# Sheet2.net
KiCad netlist of a schematic drawn in Altium Designer
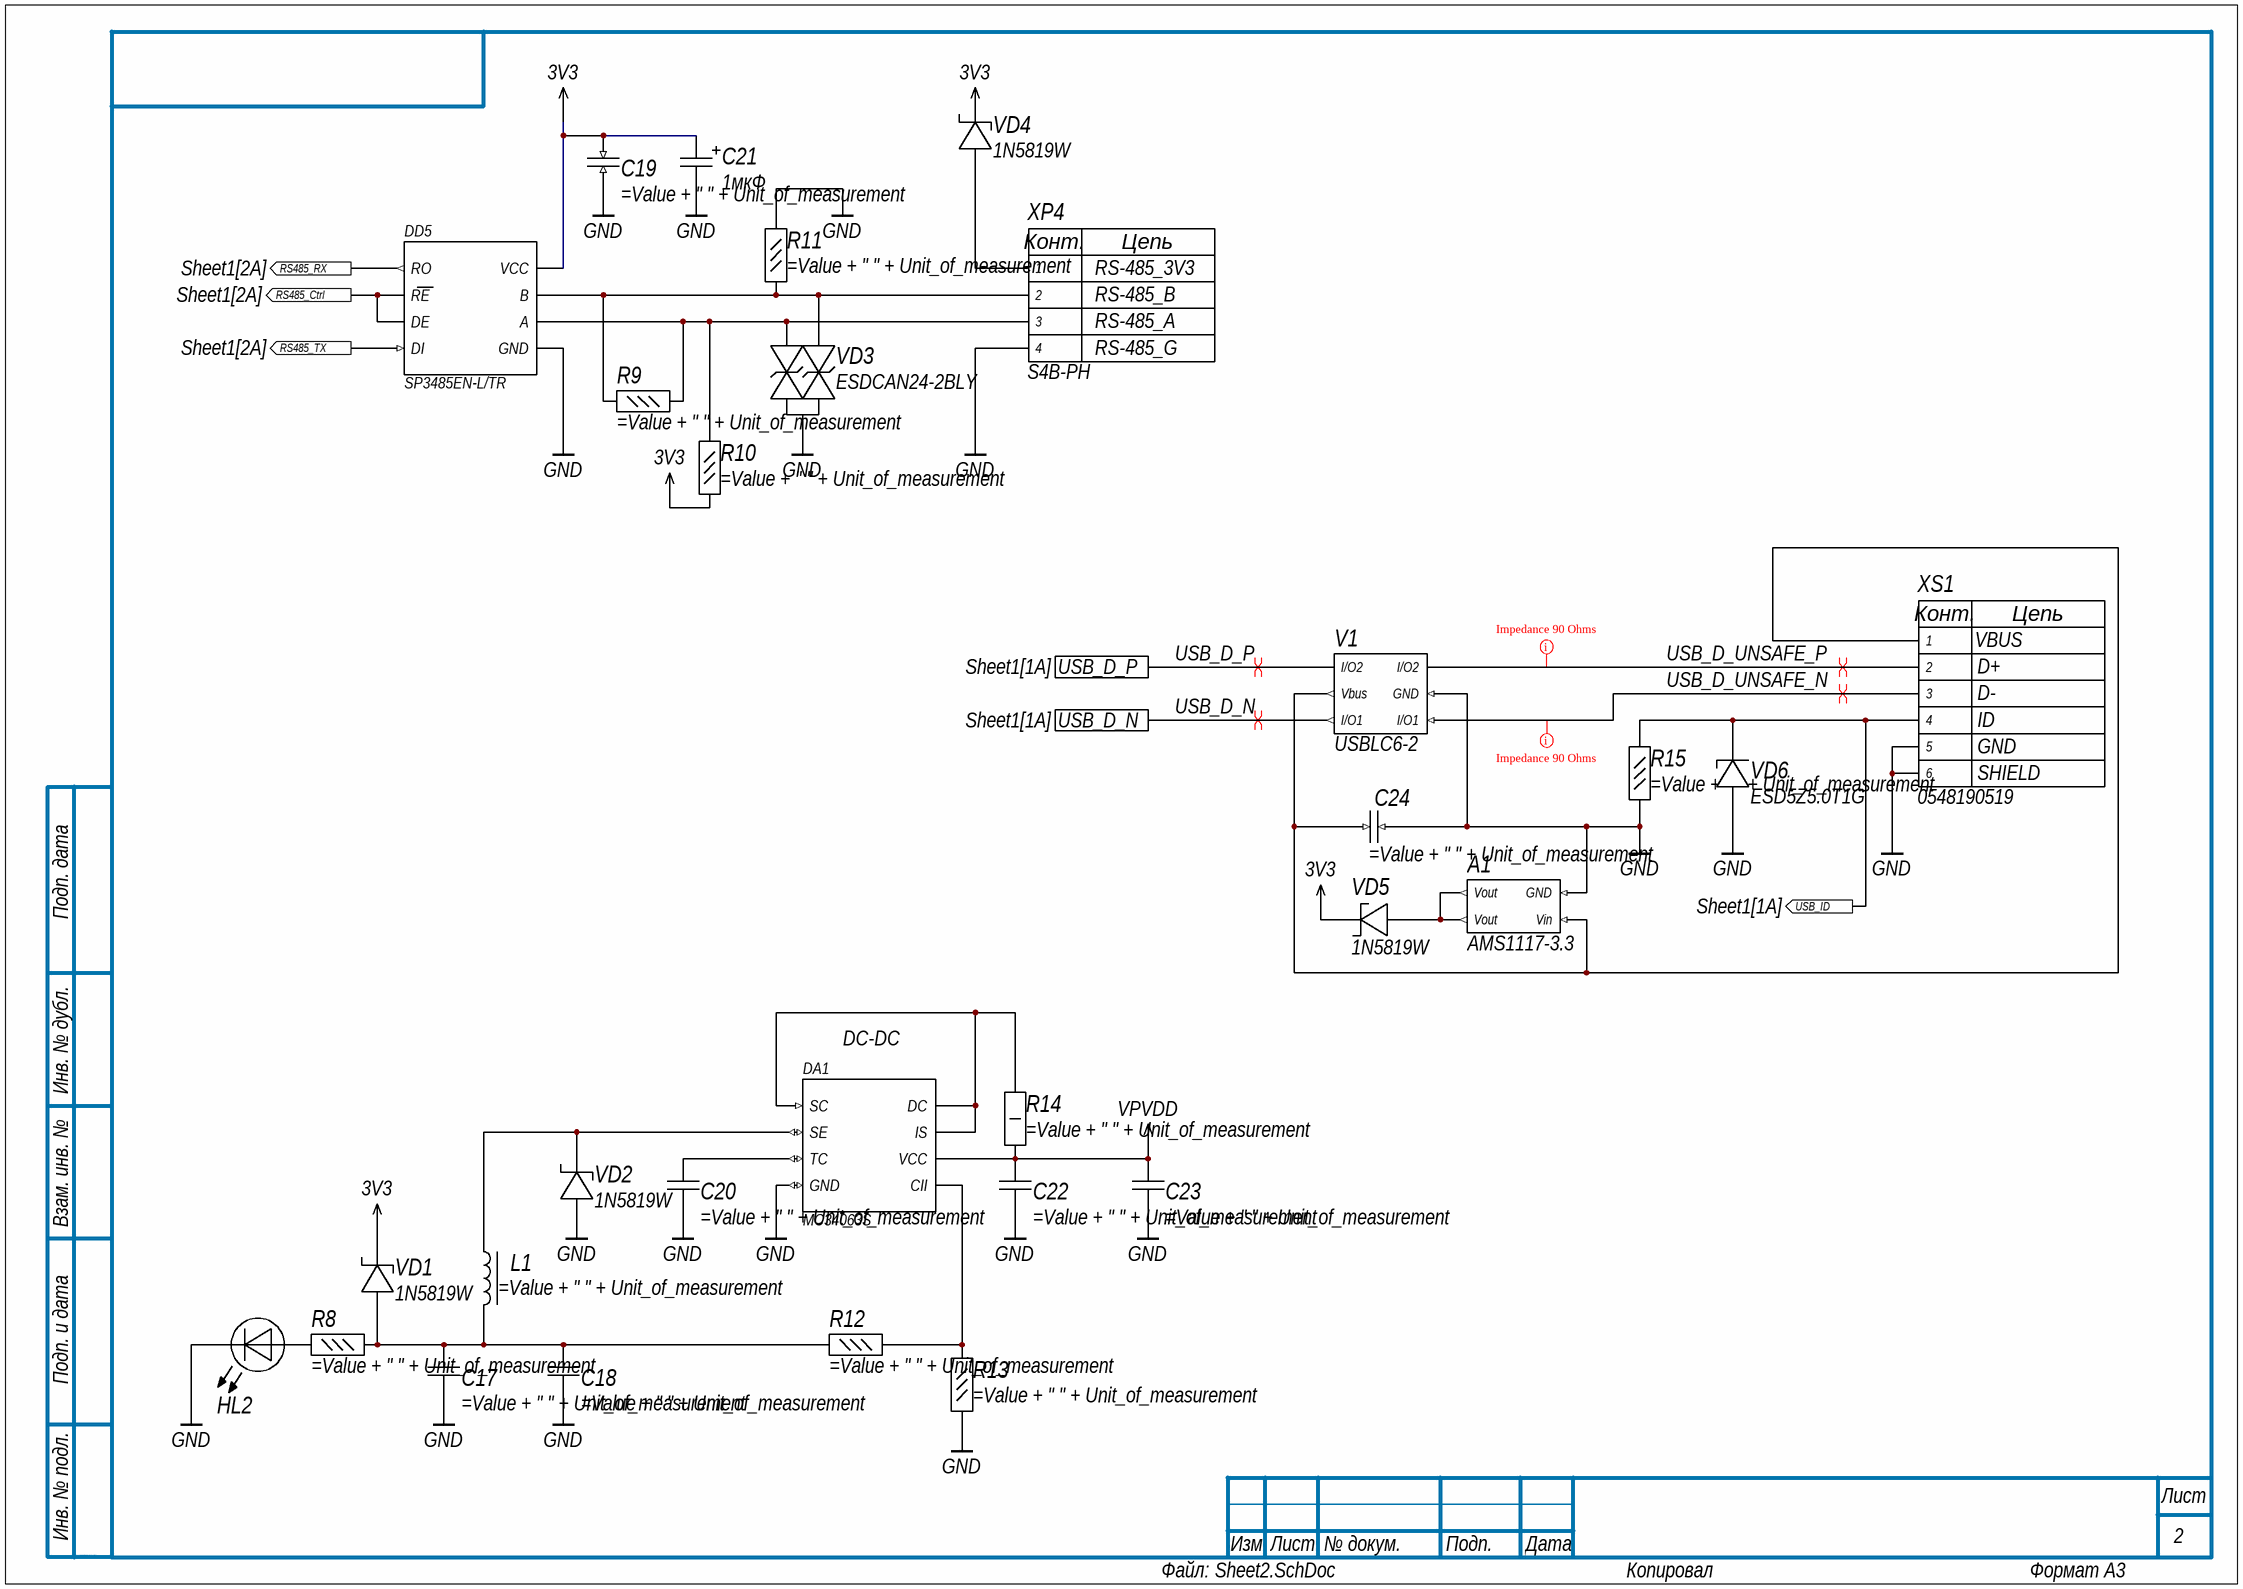
[diagram p0: Sheet2.SchDoc]

(export (version "E")
  (design (tool "Eeschema 10.0.6"))
  (components
    (comp (ref "A1")
      (value "AMS1117-3.3")
      (footprint "SOT-223")
      (description "Линейный регулятор с малым падением напряжения, 1А, 3.3В [SOT-223]")
      (libsource (lib "ICs") (part "AMS1117-3.3"))
    )
    (comp (ref "C17")
      (value "10мкФ 50В")
      (footprint "CAP_1206")
      (description "Конденсатор керамический, типоразмера 1206")
      (libsource (lib "SimpleComponents") (part "CAP_1206"))
    )
    (comp (ref "C18")
      (value "10мкФ 50В")
      (footprint "CAP_1206")
      (description "Конденсатор керамический, типоразмера 1206")
      (libsource (lib "SimpleComponents") (part "CAP_1206"))
    )
    (comp (ref "C19")
      (value "100нФ")
      (footprint "CAP_0603")
      (description "Конденсатор керамический, типоразмера 0603")
      (libsource (lib "PassiveComponents") (part "CAP_0603"))
    )
    (comp (ref "C20")
      (value "3.9нФ")
      (footprint "CAP_0603")
      (description "Конденсатор керамический, типоразмера 0603")
      (libsource (lib "SimpleComponents") (part "CAP_0603"))
    )
    (comp (ref "C21")
      (value "1мкФ")
      (footprint "TECAP_A")
      (description "Описание свойств компонента")
      (libsource (lib "PassiveComponents") (part "TECAP_A"))
    )
    (comp (ref "C22")
      (value "10мкФ 50В")
      (footprint "CAP_1206")
      (description "Конденсатор керамический, типоразмера 1206")
      (libsource (lib "SimpleComponents") (part "CAP_1206"))
    )
    (comp (ref "C23")
      (value "10мкФ 50В")
      (footprint "CAP_1206")
      (description "Конденсатор керамический, типоразмера 1206")
      (libsource (lib "SimpleComponents") (part "CAP_1206"))
    )
    (comp (ref "C24")
      (value "100нФ")
      (footprint "CAP_0603")
      (description "Конденсатор керамический, типоразмера 0603")
      (libsource (lib "PassiveComponents") (part "CAP_0603"))
    )
    (comp (ref "DA1")
      (value "MC34063S")
      (footprint "SOP-8 WithoutTP")
      (libsource (lib "ICs") (part "MC34063S"))
    )
    (comp (ref "DD5")
      (value "SP3485EN-L/TR")
      (footprint "SOIC-8 WIthoutTP")
      (description "Трансивер RS485 Half-Duplex 1/1")
      (libsource (lib "ICs") (part "SP3485EN"))
    )
    (comp (ref "HL2") (value "3") (footprint "LED_0805") (libsource (lib "Complicated") (part "LED_0805_R")))
    (comp (ref "L1")
      (value "47мкГн")
      (footprint "CD54")
      (description "Резистор, типоразмера 2010")
      (libsource (lib "SimpleComponents") (part "IND_CD54"))
    )
    (comp (ref "R8")
      (value "330Ом")
      (footprint "RES_0603")
      (description "Резистор, типоразмера 0603")
      (libsource (lib "") (part "RES_0603_2"))
    )
    (comp (ref "R9")
      (value "120Ом")
      (footprint "RES_0603")
      (description "Резистор, типоразмера 0603")
      (libsource (lib "SimpleComponents") (part "RES_0603"))
    )
    (comp (ref "R10")
      (value "4.7кОм")
      (footprint "RES_0603")
      (description "Резистор, типоразмера 0603")
      (libsource (lib "") (part "RES_0603_3"))
    )
    (comp (ref "R11")
      (value "4.7кОм")
      (footprint "RES_0603")
      (description "Резистор, типоразмера 0603")
      (libsource (lib "") (part "RES_0603_1"))
    )
    (comp (ref "R12")
      (value "8.2кОм 1%")
      (footprint "RES_0603")
      (description "Резистор, типоразмера 0603")
      (libsource (lib "SimpleComponents") (part "RES_0603"))
    )
    (comp (ref "R13")
      (value "5кОм 1%")
      (footprint "RES_0603")
      (description "Резистор, типоразмера 0603")
      (libsource (lib "") (part "RES_0603_1"))
    )
    (comp (ref "R14")
      (value "0.2Ом 1%")
      (footprint "RES_2512")
      (description "Резистор, типоразмера 2512")
      (libsource (lib "SimpleComponents") (part "RES_2512"))
    )
    (comp (ref "R15")
      (value "100кОм")
      (footprint "RES_0603")
      (description "Резистор, типоразмера 0603")
      (libsource (lib "") (part "RES_0603_1"))
    )
    (comp (ref "V1")
      (value "USBLC6-2")
      (footprint "SOT23-6")
      (description "Защита интерфейса USB от электростатических разрядов [SOT-23-6]")
      (libsource (lib "ICs") (part "USBLC6-2"))
    )
    (comp (ref "VD1")
      (value "1N5819W")
      (footprint "SOD-123")
      (description "Диод Шоттки, 40 В, 0.35 А, SOD-123")
      (libsource (lib "SimpleComponents") (part "1N5819W"))
    )
    (comp (ref "VD2")
      (value "1N5819W")
      (footprint "SOD-123")
      (description "Диод Шоттки, 40 В, 0.35 А, SOD-123")
      (libsource (lib "SimpleComponents") (part "1N5819W"))
    )
    (comp (ref "VD3")
      (value "ESDCAN24-2BLY")
      (footprint "SOT23")
      (description "Устройство защиты CAN шины от ESD, 2 защитных диода [SOT-23-3]")
      (libsource (lib "Complicated") (part "ESDCAN24-2BLY"))
    )
    (comp (ref "VD4")
      (value "1N5819W")
      (footprint "SOD-123")
      (description "Диод Шоттки, 40 В, 0.35 А, SOD-123")
      (libsource (lib "SimpleComponents") (part "1N5819W"))
    )
    (comp (ref "VD5")
      (value "1N5819W")
      (footprint "SOD-123")
      (description "Диод Шоттки, 40 В, 0.35 А, SOD-123")
      (libsource (lib "Complicated") (part "1N5819W"))
    )
    (comp (ref "VD6")
      (value "ESD5Z5.0T1G")
      (footprint "SOD-523")
      (description "Устройство защиты от ESD, защитный диод, 5В [SOD-523]")
      (libsource (lib "Complicated") (part "ESD5Z5.0T1G"))
    )
    (comp (ref "XP4")
      (value "S4B-PH")
      (footprint "S4B-PH")
      (description "JST PH 4pin 2 mm pitch; horizontal; through hole OR full smd; S4B-PH-SM4-TB")
      (libsource (lib "SimpleComponents") (part "S4B-PH"))
    )
    (comp (ref "XS1")
      (value "0548190519")
      (footprint "USB_Mini_B_TH")
      (description "USB - mini B USB 2.0 OTG Receptacle Connector 5 Position Through Hole, Right Angle")
      (libsource (lib "SimpleComponents") (part "0548190519"))
    )
  )
  (nets
    (net (code "1") (name "/RS485_Ctrl") (class "Default")
      (node (ref "DD5") (pin "2") (pinfunction "RE_2") (pintype "passive"))
      (node (ref "DD5") (pin "3") (pinfunction "DE_3") (pintype "passive"))
    )
    (net (code "2") (name "/RS485_RX") (class "Default")
      (node (ref "DD5") (pin "1") (pinfunction "RO_1") (pintype "output"))
    )
    (net (code "3") (name "/RS485_TX") (class "Default")
      (node (ref "DD5") (pin "4") (pinfunction "DI_4") (pintype "input"))
    )
    (net (code "4") (name "/USB_D_N") (class "Default")
      (node (ref "V1") (pin "6") (pinfunction "I/O1_6") (pintype "output"))
    )
    (net (code "5") (name "/USB_D_P") (class "Default")
      (node (ref "V1") (pin "4") (pinfunction "I/O2_4") (pintype "power_in"))
    )
    (net (code "6") (name "/USB_D_UNSAFE_N") (class "Default")
      (node (ref "V1") (pin "1") (pinfunction "I/O1_1") (pintype "input"))
      (node (ref "XS1") (pin "4") (pinfunction "3_4") (pintype "passive"))
    )
    (net (code "7") (name "/USB_D_UNSAFE_P") (class "Default")
      (node (ref "V1") (pin "3") (pinfunction "I/O2_3") (pintype "power_in"))
      (node (ref "XS1") (pin "3") (pinfunction "2_3") (pintype "passive"))
    )
    (net (code "8") (name "/USB_ID") (class "Default")
      (node (ref "R15") (pin "2") (pinfunction "2_2") (pintype "passive"))
      (node (ref "VD6") (pin "1") (pinfunction "1_1") (pintype "passive"))
      (node (ref "XS1") (pin "2") (pinfunction "4_2") (pintype "passive"))
    )
    (net (code "9") (name "3V3") (class "Default")
      (node (ref "C19") (pin "2") (pintype "input"))
      (node (ref "C21") (pin "1") (pintype "passive"))
      (node (ref "DD5") (pin "8") (pinfunction "VCC_8") (pintype "power_in"))
      (node (ref "R10") (pin "2") (pinfunction "2_2") (pintype "passive"))
      (node (ref "VD1") (pin "1") (pinfunction "1_1") (pintype "passive"))
      (node (ref "VD4") (pin "1") (pinfunction "1_1") (pintype "passive"))
      (node (ref "VD5") (pin "1") (pinfunction "1_1") (pintype "passive"))
    )
    (net (code "10") (name "GND") (class "Default")
      (node (ref "A1") (pin "1") (pinfunction "GND_1") (pintype "input"))
      (node (ref "C17") (pin "1") (pintype "passive"))
      (node (ref "C18") (pin "1") (pintype "passive"))
      (node (ref "C19") (pin "1") (pintype "input"))
      (node (ref "C20") (pin "1") (pintype "passive"))
      (node (ref "C21") (pin "2") (pintype "passive"))
      (node (ref "C22") (pin "1") (pintype "passive"))
      (node (ref "C23") (pin "1") (pintype "passive"))
      (node (ref "C24") (pin "1") (pintype "input"))
      (node (ref "DA1") (pin "4") (pinfunction "GND_4") (pintype "bidirectional"))
      (node (ref "DD5") (pin "5") (pinfunction "GND_5") (pintype "power_in"))
      (node (ref "HL2") (pin "C") (pinfunction "1_C") (pintype "passive"))
      (node (ref "R11") (pin "2") (pinfunction "2_2") (pintype "passive"))
      (node (ref "R13") (pin "1") (pinfunction "1_1") (pintype "passive"))
      (node (ref "R15") (pin "1") (pinfunction "1_1") (pintype "passive"))
      (node (ref "V1") (pin "2") (pinfunction "GND_2") (pintype "input"))
      (node (ref "VD2") (pin "2") (pinfunction "2_2") (pintype "passive"))
      (node (ref "VD3") (pin "3") (pinfunction "3_3") (pintype "passive"))
      (node (ref "VD6") (pin "2") (pinfunction "2_2") (pintype "passive"))
      (node (ref "XP4") (pin "4") (pinfunction "4_4") (pintype "passive"))
      (node (ref "XS1") (pin "1") (pinfunction "5_1") (pintype "passive"))
      (node (ref "XS1") (pin "6") (pinfunction "6_6") (pintype "passive"))
    )
    (net (code "11") (name "Net-(A1-Vin)") (class "Default")
      (node (ref "A1") (pin "3") (pinfunction "Vin_3") (pintype "input"))
      (node (ref "C24") (pin "2") (pintype "input"))
      (node (ref "V1") (pin "5") (pinfunction "Vbus_5") (pintype "output"))
      (node (ref "XS1") (pin "5") (pinfunction "1_5") (pintype "passive"))
    )
    (net (code "12") (name "Net-(A1-Vout-Pad2)") (class "Default")
      (node (ref "A1") (pin "2") (pinfunction "Vout_2") (pintype "output"))
      (node (ref "A1") (pin "4") (pinfunction "Vout_4") (pintype "output"))
      (node (ref "VD5") (pin "2") (pinfunction "2_2") (pintype "passive"))
    )
    (net (code "13") (name "Net-(C17-Pad2)") (class "Default")
      (node (ref "C17") (pin "2") (pintype "passive"))
      (node (ref "C18") (pin "2") (pintype "passive"))
      (node (ref "L1") (pin "2") (pinfunction "2_2") (pintype "passive"))
      (node (ref "R12") (pin "1") (pinfunction "1_1") (pintype "passive"))
      (node (ref "R8") (pin "1") (pinfunction "1_1") (pintype "passive"))
      (node (ref "VD1") (pin "2") (pinfunction "2_2") (pintype "passive"))
    )
    (net (code "14") (name "Net-(DA1-CII)") (class "Default")
      (node (ref "DA1") (pin "5") (pinfunction "CII_5") (pintype "power_in"))
      (node (ref "R12") (pin "2") (pinfunction "2_2") (pintype "passive"))
      (node (ref "R13") (pin "2") (pinfunction "2_2") (pintype "passive"))
    )
    (net (code "15") (name "Net-(DA1-DC)") (class "Default")
      (node (ref "DA1") (pin "1") (pinfunction "SC_1") (pintype "input"))
      (node (ref "DA1") (pin "7") (pinfunction "IS_7") (pintype "power_in"))
      (node (ref "DA1") (pin "8") (pinfunction "DC_8") (pintype "power_in"))
      (node (ref "R14") (pin "2") (pinfunction "2_2") (pintype "passive"))
    )
    (net (code "16") (name "Net-(DA1-SE)") (class "Default")
      (node (ref "DA1") (pin "2") (pinfunction "SE_2") (pintype "bidirectional"))
      (node (ref "L1") (pin "1") (pinfunction "1_1") (pintype "passive"))
      (node (ref "VD2") (pin "1") (pinfunction "1_1") (pintype "passive"))
    )
    (net (code "17") (name "Net-(DA1-TC)") (class "Default")
      (node (ref "C20") (pin "2") (pintype "passive"))
      (node (ref "DA1") (pin "3") (pinfunction "TC_3") (pintype "bidirectional"))
    )
    (net (code "18") (name "Net-(DD5-A)") (class "Default")
      (node (ref "DD5") (pin "6") (pinfunction "A_6") (pintype "power_in"))
      (node (ref "R10") (pin "1") (pinfunction "1_1") (pintype "passive"))
      (node (ref "R9") (pin "2") (pinfunction "2_2") (pintype "passive"))
      (node (ref "VD3") (pin "2") (pinfunction "2_2") (pintype "passive"))
      (node (ref "XP4") (pin "3") (pinfunction "3_3") (pintype "passive"))
    )
    (net (code "19") (name "Net-(DD5-B)") (class "Default")
      (node (ref "DD5") (pin "7") (pinfunction "B_7") (pintype "power_in"))
      (node (ref "R11") (pin "1") (pinfunction "1_1") (pintype "passive"))
      (node (ref "R9") (pin "1") (pinfunction "1_1") (pintype "passive"))
      (node (ref "VD3") (pin "1") (pinfunction "1_1") (pintype "passive"))
      (node (ref "XP4") (pin "2") (pinfunction "2_2") (pintype "passive"))
    )
    (net (code "20") (name "Net-(HL2-2)") (class "Default")
      (node (ref "HL2") (pin "A") (pinfunction "2_A") (pintype "passive"))
      (node (ref "R8") (pin "2") (pinfunction "2_2") (pintype "passive"))
    )
    (net (code "21") (name "Net-(VD4-Pad2)") (class "Default")
      (node (ref "VD4") (pin "2") (pinfunction "2_2") (pintype "passive"))
      (node (ref "XP4") (pin "1") (pinfunction "1_1") (pintype "passive"))
    )
    (net (code "22") (name "VPVDD") (class "Default")
      (node (ref "C22") (pin "2") (pintype "passive"))
      (node (ref "C23") (pin "2") (pintype "passive"))
      (node (ref "DA1") (pin "6") (pinfunction "VCC_6") (pintype "power_in"))
      (node (ref "R14") (pin "1") (pinfunction "1_1") (pintype "passive"))
    )
  )
)
